# ZenDriver_Master.net
KiCad netlist of a schematic drawn in Altium Designer
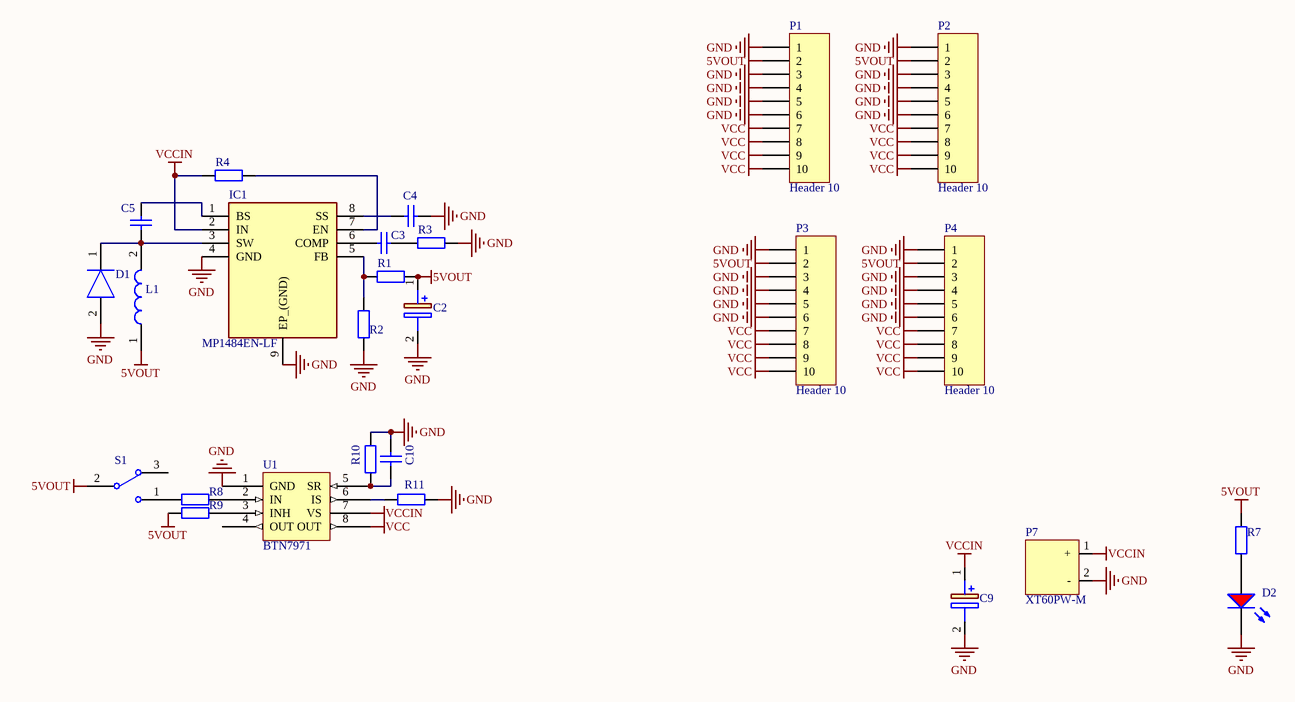
[diagram p0: ZenDriver_Master.SchDoc]

(export (version "E")
  (design (tool "Eeschema 10.0.6"))
  (components
    (comp (ref "C2")
      (value "10uF 4.5V tan")
      (footprint "SamacSys:CAPPM7343X310N")
      (description "T494D106K035AH")
      (fields (field (name "MOUSER PART NUMBER") "80-T494D106K035AH"))
      (libsource (lib "*") (part "T494D106K035AH"))
    )
    (comp (ref "C3")
      (value "6.8nF (682) 10% 50V")
      (footprint "0603_C")
      (description "贴片电容")
      (libsource (lib "Miscellaneous Devices LC") (part "0603 6.8nF (682) 10% 50V"))
    )
    (comp (ref "C4")
      (value "100nF (104) 10% 50V")
      (footprint "0603_C")
      (description "贴片电容")
      (libsource (lib "Miscellaneous Devices LC") (part "0603 100nF (104) 10% 50V"))
    )
    (comp (ref "C5")
      (value "10nF (103) 10% 50V")
      (footprint "0603_C")
      (description "贴片电容")
      (libsource (lib "Miscellaneous Devices LC") (part "0603 10nF (103) 10% 50V"))
    )
    (comp (ref "C9")
      (value "1000uf 25v")
      (footprint "SamacSys:CAPAE1350X1400N")
      (description "Capacitor Polarised")
      (fields
        (field (name "MANUFACTURER_PART_NUMBER") "865060462010")
        (field (name "MOUSER PART NUMBER") "710-865060462010")
      )
      (libsource (lib "*") (part "865060462010"))
    )
    (comp (ref "C10")
      (value "100nF (104) 10% 50V")
      (footprint "0603_C")
      (description "贴片电容")
      (libsource (lib "Miscellaneous Devices LC") (part "0603 100nF (104) 10% 50V"))
    )
    (comp (ref "D1")
      (value "B130LAW-7-F")
      (footprint "SamacSys:SOD3716X145N")
      (description "Diode")
      (fields (field (name "MOUSER PART NUMBER") "621-B130LAW-F") (field (name "RS PART NUMBER") "7513193P"))
      (libsource (lib "*") (part "B130LAW-7-F"))
    )
    (comp (ref "D2")
      (value "红灯 0603")
      (footprint "0603_LED_S1")
      (description "发光二极管")
      (libsource (lib "Miscellaneous Devices LC") (part "0603 红灯"))
    )
    (comp (ref "IC1")
      (value "MP1484EN-LF")
      (footprint "SamacSys:SOIC127P600X170-9N")
      (description "Integrated Circuit")
      (fields (field (name "MOUSER PART NUMBER") "946-MP1484ENLF"))
      (libsource (lib "*") (part "MP1484EN-LF"))
    )
    (comp (ref "L1")
      (value "1040 10UH 5A")
      (footprint "SamacSys:74404064470")
      (description "Inductor")
      (fields
        (field (name "MANUFACTURER_PART_NUMBER") "74404064100")
        (field (name "MOUSER PART NUMBER") "710-74404064100")
      )
      (libsource (lib "*") (part "74404064100"))
    )
    (comp (ref "P1")
      (value "Header 10")
      (footprint "HDR1X10")
      (description "Header, 10-Pin")
      (fields (field (name "PUBLISHER") "Altium Limited"))
      (libsource (lib "Miscellaneous Connectors") (part "Header 10"))
    )
    (comp (ref "P2")
      (value "Header 10")
      (footprint "HDR1X10")
      (description "Header, 10-Pin")
      (fields (field (name "PUBLISHER") "Altium Limited"))
      (libsource (lib "Miscellaneous Connectors") (part "Header 10"))
    )
    (comp (ref "P3")
      (value "Header 10")
      (footprint "HDR1X10")
      (description "Header, 10-Pin")
      (fields (field (name "PUBLISHER") "Altium Limited"))
      (libsource (lib "Miscellaneous Connectors") (part "Header 10"))
    )
    (comp (ref "P4")
      (value "Header 10")
      (footprint "HDR1X10")
      (description "Header, 10-Pin")
      (fields (field (name "PUBLISHER") "Altium Limited"))
      (libsource (lib "Miscellaneous Connectors") (part "Header 10"))
    )
    (comp (ref "P7")
      (value "XT60PW-M")
      (footprint "XT60PW-M")
      (description "XT60")
      (libsource (lib "Hare_Library") (part "XT60"))
    )
    (comp (ref "R1")
      (value "44.2K")
      (footprint "0603_R")
      (description "贴片电阻")
      (libsource (lib "Miscellaneous Devices LC") (part "0603 1.5KΩ (1501) 1%"))
    )
    (comp (ref "R2")
      (value "10KΩ (1002) ±1%")
      (footprint "0603_R")
      (description "贴片电阻")
      (libsource (lib "") (part "0603 10KΩ (1002) 1%_1"))
    )
    (comp (ref "R3")
      (value "6.8KΩ (6801) ±1%")
      (footprint "0603_R")
      (description "贴片电阻")
      (libsource (lib "Miscellaneous Devices LC") (part "0603 6.8KΩ (6801) 1%"))
    )
    (comp (ref "R4")
      (value "100KΩ (1003) ±1%")
      (footprint "0603_R")
      (description "贴片电阻")
      (libsource (lib "Miscellaneous Devices LC") (part "0603 100KΩ (1003) 1%"))
    )
    (comp (ref "R7")
      (value "4.7k")
      (footprint "0603_R")
      (description "贴片电阻")
      (libsource (lib "Miscellaneous Devices LC") (part "0603 470Ω (4700) 1%"))
    )
    (comp (ref "R8")
      (value "10KΩ (1002) ±1%")
      (footprint "0603_R")
      (description "贴片电阻")
      (libsource (lib "Miscellaneous Devices LC") (part "0603 10KΩ (1002) 1%"))
    )
    (comp (ref "R9")
      (value "10KΩ (1002) ±1%")
      (footprint "0603_R")
      (description "贴片电阻")
      (libsource (lib "Miscellaneous Devices LC") (part "0603 10KΩ (1002) 1%"))
    )
    (comp (ref "R10")
      (value "1KΩ (1001) ±1%")
      (footprint "0603_R")
      (description "贴片电阻")
      (libsource (lib "Miscellaneous Devices LC") (part "0603 1KΩ (1001) 1%"))
    )
    (comp (ref "R11")
      (value "2KΩ (2001) ±1%")
      (footprint "0603_R")
      (description "贴片电阻")
      (libsource (lib "Miscellaneous Devices LC") (part "0603 2KΩ (2001) 1%"))
    )
    (comp (ref "S1")
      (value "SW-SPDT")
      (footprint "sw_9*3.5*5.5mm")
      (description "SPDT Subminiature Toggle Switch, Right Angle Mounting, Vertical Actuation")
      (fields (field (name "PUBLISHER") "Altium Limited"))
      (libsource (lib "Miscellaneous Devices") (part "SW-SPDT"))
    )
    (comp (ref "U1")
      (value "BTN7971")
      (footprint "DPAK127P1615X127-8N")
      (libsource (lib "Sheet2") (part "BTN7971"))
    )
  )
  (nets
    (net (code "1") (name "5VOUT") (class "Default")
      (node (ref "C2") (pin "1") (pinfunction "+_1") (pintype "passive"))
      (node (ref "L1") (pin "1") (pinfunction "1_1") (pintype "passive"))
      (node (ref "P1") (pin "2") (pinfunction "2_2") (pintype "passive"))
      (node (ref "P2") (pin "2") (pinfunction "2_2") (pintype "passive"))
      (node (ref "P3") (pin "2") (pinfunction "2_2") (pintype "passive"))
      (node (ref "P4") (pin "2") (pinfunction "2_2") (pintype "passive"))
      (node (ref "R1") (pin "2") (pinfunction "2_2") (pintype "passive"))
      (node (ref "R7") (pin "2") (pinfunction "2_2") (pintype "passive"))
      (node (ref "R9") (pin "1") (pinfunction "1_1") (pintype "passive"))
      (node (ref "S1") (pin "2") (pinfunction "2_2") (pintype "passive"))
    )
    (net (code "2") (name "GND") (class "Default")
      (node (ref "C10") (pin "2") (pinfunction "2_2") (pintype "passive"))
      (node (ref "C2") (pin "2") (pinfunction "-_2") (pintype "passive"))
      (node (ref "C4") (pin "2") (pinfunction "2_2") (pintype "passive"))
      (node (ref "C9") (pin "2") (pinfunction "+_2") (pintype "passive"))
      (node (ref "D1") (pin "2") (pinfunction "A_2") (pintype "passive"))
      (node (ref "D2") (pin "K") (pinfunction "K_K") (pintype "passive"))
      (node (ref "IC1") (pin "4") (pinfunction "GND_4") (pintype "passive"))
      (node (ref "IC1") (pin "9") (pinfunction "EP_(GND)_9") (pintype "passive"))
      (node (ref "P1") (pin "1") (pinfunction "1_1") (pintype "passive"))
      (node (ref "P1") (pin "3") (pinfunction "3_3") (pintype "passive"))
      (node (ref "P1") (pin "4") (pinfunction "4_4") (pintype "passive"))
      (node (ref "P1") (pin "5") (pinfunction "5_5") (pintype "passive"))
      (node (ref "P1") (pin "6") (pinfunction "6_6") (pintype "passive"))
      (node (ref "P2") (pin "1") (pinfunction "1_1") (pintype "passive"))
      (node (ref "P2") (pin "3") (pinfunction "3_3") (pintype "passive"))
      (node (ref "P2") (pin "4") (pinfunction "4_4") (pintype "passive"))
      (node (ref "P2") (pin "5") (pinfunction "5_5") (pintype "passive"))
      (node (ref "P2") (pin "6") (pinfunction "6_6") (pintype "passive"))
      (node (ref "P3") (pin "1") (pinfunction "1_1") (pintype "passive"))
      (node (ref "P3") (pin "3") (pinfunction "3_3") (pintype "passive"))
      (node (ref "P3") (pin "4") (pinfunction "4_4") (pintype "passive"))
      (node (ref "P3") (pin "5") (pinfunction "5_5") (pintype "passive"))
      (node (ref "P3") (pin "6") (pinfunction "6_6") (pintype "passive"))
      (node (ref "P4") (pin "1") (pinfunction "1_1") (pintype "passive"))
      (node (ref "P4") (pin "3") (pinfunction "3_3") (pintype "passive"))
      (node (ref "P4") (pin "4") (pinfunction "4_4") (pintype "passive"))
      (node (ref "P4") (pin "5") (pinfunction "5_5") (pintype "passive"))
      (node (ref "P4") (pin "6") (pinfunction "6_6") (pintype "passive"))
      (node (ref "P7") (pin "2") (pinfunction "-_2") (pintype "passive"))
      (node (ref "R10") (pin "2") (pinfunction "2_2") (pintype "passive"))
      (node (ref "R11") (pin "1") (pinfunction "1_1") (pintype "passive"))
      (node (ref "R2") (pin "1") (pinfunction "1_1") (pintype "passive"))
      (node (ref "R3") (pin "2") (pinfunction "2_2") (pintype "passive"))
      (node (ref "U1") (pin "1") (pinfunction "GND_1") (pintype "passive"))
    )
    (net (code "3") (name "Net-(C3-Pad2)") (class "Default")
      (node (ref "C3") (pin "2") (pinfunction "2_2") (pintype "passive"))
      (node (ref "R3") (pin "1") (pinfunction "1_1") (pintype "passive"))
    )
    (net (code "4") (name "Net-(D1-K)") (class "Default")
      (node (ref "C5") (pin "1") (pinfunction "1_1") (pintype "passive"))
      (node (ref "D1") (pin "1") (pinfunction "K_1") (pintype "passive"))
      (node (ref "IC1") (pin "3") (pinfunction "SW_3") (pintype "passive"))
      (node (ref "L1") (pin "2") (pinfunction "2_2") (pintype "passive"))
    )
    (net (code "5") (name "Net-(D2-PadA)") (class "Default")
      (node (ref "D2") (pin "A") (pinfunction "A_A") (pintype "passive"))
      (node (ref "R7") (pin "1") (pinfunction "1_1") (pintype "passive"))
    )
    (net (code "6") (name "Net-(IC1-BS)") (class "Default")
      (node (ref "C5") (pin "2") (pinfunction "2_2") (pintype "passive"))
      (node (ref "IC1") (pin "1") (pinfunction "BS_1") (pintype "passive"))
    )
    (net (code "7") (name "Net-(IC1-COMP)") (class "Default")
      (node (ref "C3") (pin "1") (pinfunction "1_1") (pintype "passive"))
      (node (ref "IC1") (pin "6") (pinfunction "COMP_6") (pintype "passive"))
    )
    (net (code "8") (name "Net-(IC1-EN)") (class "Default")
      (node (ref "IC1") (pin "7") (pinfunction "EN_7") (pintype "passive"))
      (node (ref "R4") (pin "2") (pinfunction "2_2") (pintype "passive"))
    )
    (net (code "9") (name "Net-(IC1-FB)") (class "Default")
      (node (ref "IC1") (pin "5") (pinfunction "FB_5") (pintype "passive"))
      (node (ref "R1") (pin "1") (pinfunction "1_1") (pintype "passive"))
      (node (ref "R2") (pin "2") (pinfunction "2_2") (pintype "passive"))
    )
    (net (code "10") (name "Net-(IC1-SS)") (class "Default")
      (node (ref "C4") (pin "1") (pinfunction "1_1") (pintype "passive"))
      (node (ref "IC1") (pin "8") (pinfunction "SS_8") (pintype "passive"))
    )
    (net (code "11") (name "Net-(R8-Pad1)") (class "Default")
      (node (ref "R8") (pin "1") (pinfunction "1_1") (pintype "passive"))
      (node (ref "S1") (pin "1") (pinfunction "1_1") (pintype "passive"))
    )
    (net (code "12") (name "Net-(U1-IN)") (class "Default")
      (node (ref "R8") (pin "2") (pinfunction "2_2") (pintype "passive"))
      (node (ref "U1") (pin "2") (pinfunction "IN_2") (pintype "input"))
    )
    (net (code "13") (name "Net-(U1-INH)") (class "Default")
      (node (ref "R9") (pin "2") (pinfunction "2_2") (pintype "passive"))
      (node (ref "U1") (pin "3") (pinfunction "INH_3") (pintype "input"))
    )
    (net (code "14") (name "Net-(U1-IS)") (class "Default")
      (node (ref "R11") (pin "2") (pinfunction "2_2") (pintype "passive"))
      (node (ref "U1") (pin "6") (pinfunction "IS_6") (pintype "output"))
    )
    (net (code "15") (name "Net-(U1-SR)") (class "Default")
      (node (ref "C10") (pin "1") (pinfunction "1_1") (pintype "passive"))
      (node (ref "R10") (pin "1") (pinfunction "1_1") (pintype "passive"))
      (node (ref "U1") (pin "5") (pinfunction "SR_5") (pintype "input"))
    )
    (net (code "16") (name "VCC") (class "Default")
      (node (ref "P1") (pin "10") (pinfunction "10_10") (pintype "passive"))
      (node (ref "P1") (pin "7") (pinfunction "7_7") (pintype "passive"))
      (node (ref "P1") (pin "8") (pinfunction "8_8") (pintype "passive"))
      (node (ref "P1") (pin "9") (pinfunction "9_9") (pintype "passive"))
      (node (ref "P2") (pin "10") (pinfunction "10_10") (pintype "passive"))
      (node (ref "P2") (pin "7") (pinfunction "7_7") (pintype "passive"))
      (node (ref "P2") (pin "8") (pinfunction "8_8") (pintype "passive"))
      (node (ref "P2") (pin "9") (pinfunction "9_9") (pintype "passive"))
      (node (ref "P3") (pin "10") (pinfunction "10_10") (pintype "passive"))
      (node (ref "P3") (pin "7") (pinfunction "7_7") (pintype "passive"))
      (node (ref "P3") (pin "8") (pinfunction "8_8") (pintype "passive"))
      (node (ref "P3") (pin "9") (pinfunction "9_9") (pintype "passive"))
      (node (ref "P4") (pin "10") (pinfunction "10_10") (pintype "passive"))
      (node (ref "P4") (pin "7") (pinfunction "7_7") (pintype "passive"))
      (node (ref "P4") (pin "8") (pinfunction "8_8") (pintype "passive"))
      (node (ref "P4") (pin "9") (pinfunction "9_9") (pintype "passive"))
      (node (ref "U1") (pin "8") (pinfunction "OUT_8") (pintype "output"))
    )
    (net (code "17") (name "VCCIN") (class "Default")
      (node (ref "C9") (pin "1") (pinfunction "-_1") (pintype "passive"))
      (node (ref "IC1") (pin "2") (pinfunction "IN_2") (pintype "passive"))
      (node (ref "P7") (pin "1") (pinfunction "+_1") (pintype "passive"))
      (node (ref "R4") (pin "1") (pinfunction "1_1") (pintype "passive"))
      (node (ref "U1") (pin "7") (pinfunction "VS_7") (pintype "passive"))
    )
    (net (code "18") (name "unconnected-(S1-Pad3)") (class "Default")
      (node (ref "S1") (pin "3") (pinfunction "3_3") (pintype "passive"))
    )
    (net (code "19") (name "unconnected-(U1-OUT-Pad4)") (class "Default")
      (node (ref "U1") (pin "4") (pinfunction "OUT_4") (pintype "output"))
    )
  )
)
